# Control.net
KiCad netlist of a schematic drawn in EasyEDA Pro
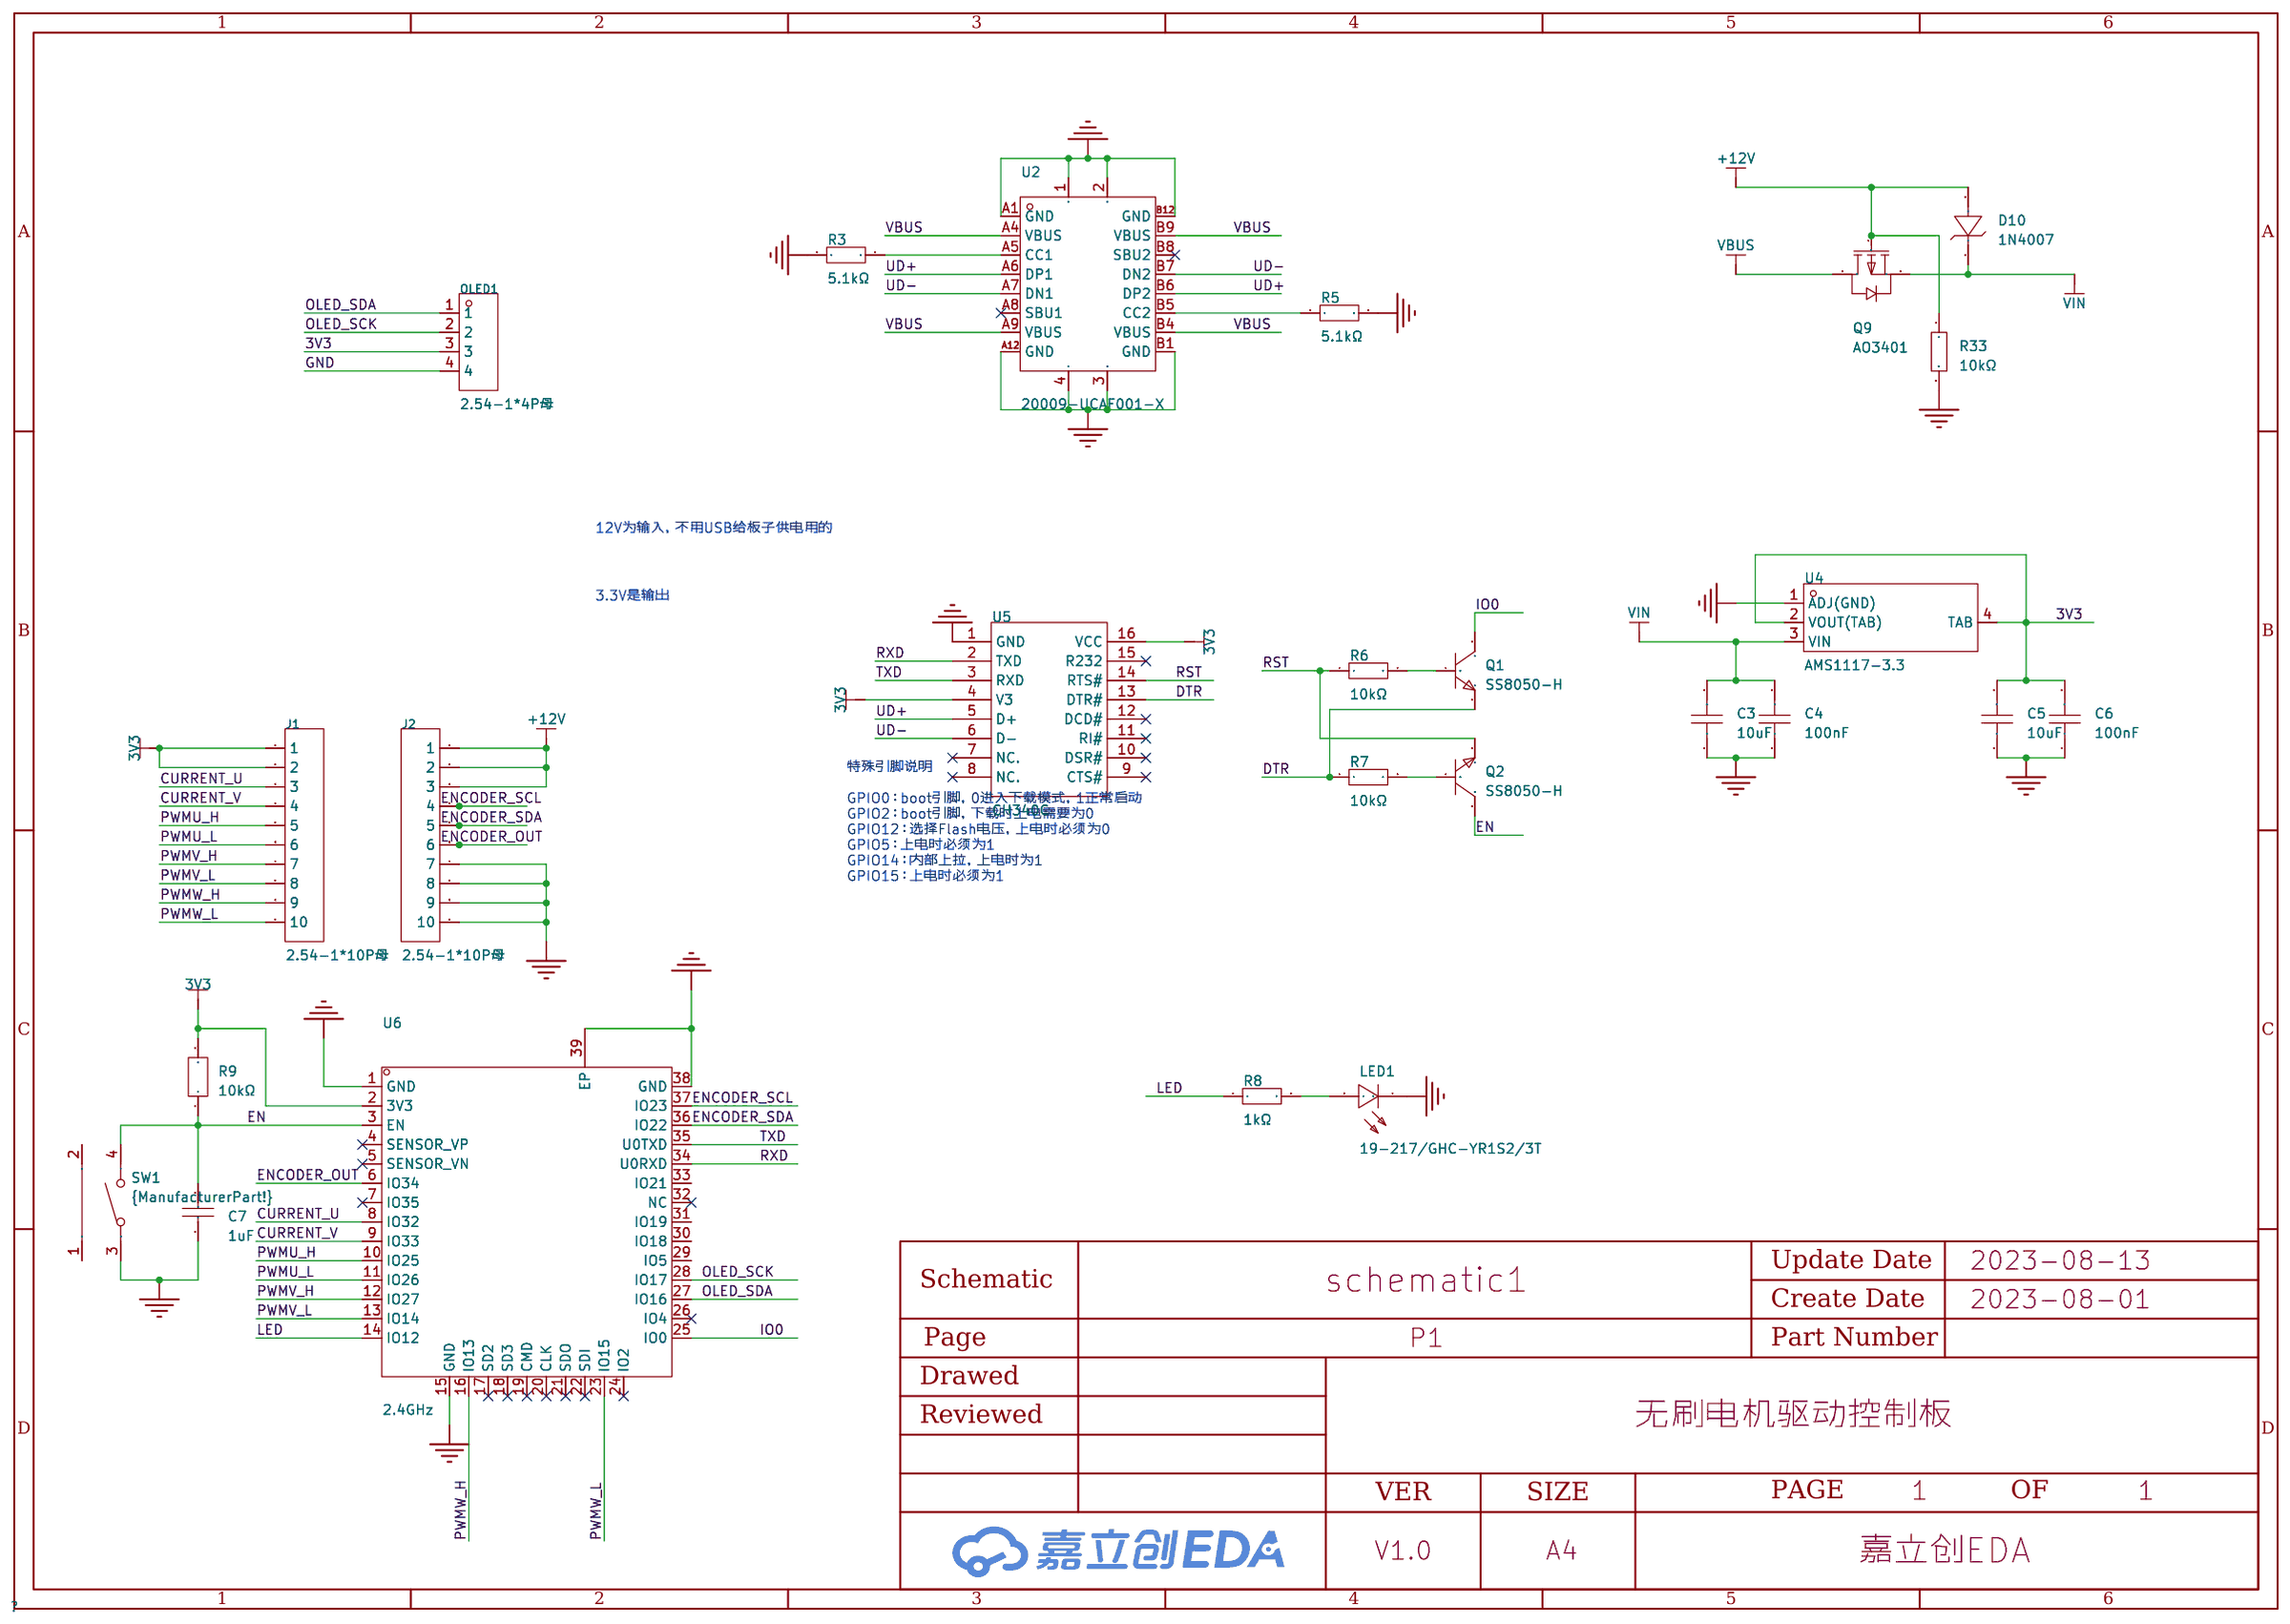
[diagram p0: schematic sheet]

(export (version "E")
  (design (tool "Eeschema 10.0.6"))
  (components
    (comp (ref "C3")
      (value "10uF")
      (footprint "easyedapro:C0603")
      (description "容值:10uF;精度:±20%;额定电压:25V;材质(温度系数):X5R;")
      (fields
        (field (name "Manufacturer Part") "CL10A106MA8NRNC")
        (field (name "Manufacturer") "SAMSUNG(三星)")
      )
      (libsource (lib "easyedapro") (part "CL10A106MA8NRNC"))
    )
    (comp (ref "C4")
      (value "100nF")
      (footprint "easyedapro:C0603")
      (description "容值:100nF;精度:±10%;额定电压:50V;材质(温度系数):X7R;")
      (fields
        (field (name "Manufacturer Part") "CC0603KRX7R9BB104")
        (field (name "Manufacturer") "YAGEO(国巨)")
      )
      (libsource (lib "easyedapro") (part "CC0603KRX7R9BB104"))
    )
    (comp (ref "C5")
      (value "10uF")
      (footprint "easyedapro:C0603")
      (description "容值:10uF;精度:±20%;额定电压:25V;材质(温度系数):X5R;")
      (fields
        (field (name "Manufacturer Part") "CL10A106MA8NRNC")
        (field (name "Manufacturer") "SAMSUNG(三星)")
      )
      (libsource (lib "easyedapro") (part "CL10A106MA8NRNC"))
    )
    (comp (ref "C6")
      (value "100nF")
      (footprint "easyedapro:C0603")
      (description "容值:100nF;精度:±10%;额定电压:50V;材质(温度系数):X7R;")
      (fields
        (field (name "Manufacturer Part") "CC0603KRX7R9BB104")
        (field (name "Manufacturer") "YAGEO(国巨)")
      )
      (libsource (lib "easyedapro") (part "CC0603KRX7R9BB104"))
    )
    (comp (ref "C7")
      (value "1uF")
      (footprint "easyedapro:C0603")
      (description "容值:1uF;精度:±10%;额定电压:50V;材质(温度系数):X5R;")
      (fields
        (field (name "Manufacturer Part") "CL10A105KB8NNNC")
        (field (name "Manufacturer") "SAMSUNG(三星)")
      )
      (libsource (lib "easyedapro") (part "CL10A105KB8NNNC"))
    )
    (comp (ref "D10")
      (value "1N4007")
      (footprint "easyedapro:SOD-123FL_L2.7-W1.8-LS3.8-RD")
      (description "二极管配置:独立式;直流反向耐压(Vr):1kV;平均整流电流(Io):1A;正向压降(Vf):1.1V@1A;反向电流(Ir):10uA@1kV;")
      (fields (field (name "Manufacturer") "TWGMC(台湾迪嘉)"))
      (libsource (lib "easyedapro") (part "1N4007_C727082"))
    )
    (comp (ref "J1")
      (value "2.54-1*10P母")
      (footprint "easyedapro:HDR-TH_10P-P2.54-V-F")
      (description "排数:单排;总孔位数:10;间距:2.54mm;插孔结构:1x10P;行距:-;安装类型:直插;塑高:-;触头材质:-;触头镀层:-;")
      (fields (field (name "Manufacturer") "BOOMELE(博穆精密)"))
      (libsource (lib "easyedapro") (part "Header-Female-2.54_1x10"))
    )
    (comp (ref "J2")
      (value "2.54-1*10P母")
      (footprint "easyedapro:HDR-TH_10P-P2.54-V-F")
      (description "排数:单排;总孔位数:10;间距:2.54mm;插孔结构:1x10P;行距:-;安装类型:直插;塑高:-;触头材质:-;触头镀层:-;")
      (fields (field (name "Manufacturer") "BOOMELE(博穆精密)"))
      (libsource (lib "easyedapro") (part "Header-Female-2.54_1x10"))
    )
    (comp (ref "LED1")
      (value "19-217/GHC-YR1S2/3T")
      (footprint "easyedapro:LED0603-RD")
      (description "发光颜色:翠绿;二极管配置:-;主波长:520nm~535nm;色温:-;功率:110mW;安装方式:-;")
      (fields (field (name "Manufacturer") "EVERLIGHT(亿光)"))
      (libsource (lib "easyedapro") (part "19-217/GHC-YR1S2/3T"))
    )
    (comp (ref "OLED1")
      (value "2.54-1*4P母")
      (footprint "easyedapro:HDR-TH_4P-P2.54-V-F")
      (fields (field (name "Manufacturer") "BOOMELE(博穆精密)"))
      (libsource (lib "easyedapro") (part "2.54-1*4P母"))
    )
    (comp (ref "Q1")
      (value "SS8050-H")
      (footprint "easyedapro:SOT-23-3_L2.9-W1.3-P1.90-LS2.4-BR")
      (description "晶体管类型:NPN;集射极击穿电压(Vceo):25V;集电极电流(Ic):1.5A;功率(Pd):300mW;直流电流增益(hFE@Ic,Vce):200@100mA,1V;")
      (fields (field (name "Manufacturer") "YANGJIE(扬杰)"))
      (libsource (lib "easyedapro") (part "SS8050-H"))
    )
    (comp (ref "Q2")
      (value "SS8050-H")
      (footprint "easyedapro:SOT-23-3_L2.9-W1.3-P1.90-LS2.4-BR")
      (description "晶体管类型:NPN;集射极击穿电压(Vceo):25V;集电极电流(Ic):1.5A;功率(Pd):300mW;直流电流增益(hFE@Ic,Vce):200@100mA,1V;")
      (fields (field (name "Manufacturer") "YANGJIE(扬杰)"))
      (libsource (lib "easyedapro") (part "SS8050-H"))
    )
    (comp (ref "Q9")
      (value "AO3401")
      (footprint "easyedapro:SOT-23-3_L2.9-W1.4-P1.90-LS2.6-BR")
      (description "类型:P沟道;漏源电压(Vdss):30V;连续漏极电流(Id):4.2A;功率(Pd):350mW;导通电阻(RDS(on)@Vgs,Id):65mΩ@10V,4.2A;")
      (fields (field (name "Manufacturer") "TWGMC(台湾迪嘉)"))
      (libsource (lib "easyedapro") (part "AO3401_C727156"))
    )
    (comp (ref "R3")
      (value "5.1kΩ")
      (footprint "easyedapro:R0603")
      (description "电阻类型:厚膜电阻;阻值:5.1kΩ;精度:±1%;功率:100mW;")
      (fields
        (field (name "Manufacturer Part") "0603WAF5101T5E")
        (field (name "Manufacturer") "UNI-ROYAL(厚声)")
      )
      (libsource (lib "easyedapro") (part "0603WAF5101T5E"))
    )
    (comp (ref "R5")
      (value "5.1kΩ")
      (footprint "easyedapro:R0603")
      (description "电阻类型:厚膜电阻;阻值:5.1kΩ;精度:±1%;功率:100mW;")
      (fields
        (field (name "Manufacturer Part") "0603WAF5101T5E")
        (field (name "Manufacturer") "UNI-ROYAL(厚声)")
      )
      (libsource (lib "easyedapro") (part "0603WAF5101T5E"))
    )
    (comp (ref "R6")
      (value "10kΩ")
      (footprint "easyedapro:R0603")
      (description "电阻类型:厚膜电阻;阻值:10kΩ;精度:±1%;功率:100mW;")
      (fields (field (name "Manufacturer Part") "ERJ3EKF1002V") (field (name "Manufacturer") "PANASONIC(松下)"))
      (libsource (lib "easyedapro") (part "ERJ-3EKF1002V"))
    )
    (comp (ref "R7")
      (value "10kΩ")
      (footprint "easyedapro:R0603")
      (description "电阻类型:厚膜电阻;阻值:10kΩ;精度:±1%;功率:100mW;")
      (fields (field (name "Manufacturer Part") "ERJ3EKF1002V") (field (name "Manufacturer") "PANASONIC(松下)"))
      (libsource (lib "easyedapro") (part "ERJ-3EKF1002V"))
    )
    (comp (ref "R8")
      (value "1kΩ")
      (footprint "easyedapro:R0603")
      (description "电阻类型:厚膜电阻;阻值:1kΩ;精度:±1%;功率:100mW;")
      (fields
        (field (name "Manufacturer Part") "0603WAF1001T5E")
        (field (name "Manufacturer") "UNI-ROYAL(厚声)")
      )
      (libsource (lib "easyedapro") (part "0603WAF1001T5E"))
    )
    (comp (ref "R9")
      (value "10kΩ")
      (footprint "easyedapro:R0603")
      (description "阻值:10kΩ;精度:±1%;功率:-;")
      (fields (field (name "Manufacturer Part") "SG73P1JTTD1002F") (field (name "Manufacturer") "KOA"))
      (libsource (lib "easyedapro") (part "SG73P1JTTD1002F"))
    )
    (comp (ref "R33")
      (value "10kΩ")
      (footprint "easyedapro:R0603")
      (description "电阻类型:厚膜电阻;阻值:10kΩ;精度:±1%;功率:100mW;")
      (fields
        (field (name "Manufacturer Part") "0603WAF1002T5E")
        (field (name "Manufacturer") "UNI-ROYAL(厚声)")
      )
      (libsource (lib "easyedapro") (part "0603WAF1002T5E"))
    )
    (comp (ref "SW1")
      (value "{ManufacturerPart!}")
      (footprint "easyedapro:SW-SMD_TS24CA")
      (description "触点电流:50mA;额定电压(DC):12V;电路结构:单刀单掷;安装方式:卧贴;带灯:-;机械寿命:-;")
      (fields (field (name "Manufacturer Part") "TS24CA") (field (name "Manufacturer") "SHOUHAN(首韩)"))
      (libsource (lib "easyedapro") (part "TS24CA"))
    )
    (comp (ref "U2")
      (value "20009-UCAF001-X")
      (footprint "easyedapro:TYPE-C-SMD_20009-UCAF001-X")
      (fields (field (name "Manufacturer") "MINTRON(明硕)"))
      (libsource (lib "easyedapro") (part "20009-UCAF001-X"))
    )
    (comp (ref "U4")
      (value "AMS1117-3.3")
      (footprint "easyedapro:SOT-223-4_L6.5-W3.5-P2.30-LS7.0-BR")
      (description "输出类型:固定;输出极性:正;最大输入电压:18V;输出电压:3.3V;输出电流:1A;电源纹波抑制比(PSRR):60dB@(120Hz);")
      (fields (field (name "Manufacturer") "UMW(广东友台半导体)"))
      (libsource (lib "easyedapro") (part "AMS1117-3.3_C347222"))
    )
    (comp (ref "U5")
      (value "CH340C")
      (footprint "easyedapro:SOP-16_L10.0-W3.9-P1.27-LS6.0-BL")
      (description "应用功能:Transceiver;接口协议:USB 2.0;数据速率:2Mbps;供电电压:3.3V；5V;")
      (fields (field (name "Manufacturer") "WCH(南京沁恒)"))
      (libsource (lib "easyedapro") (part "CH340C"))
    )
    (comp (ref "U6")
      (value "2.4GHz")
      (footprint "easyedapro:WIRELM-SMD_ESP32-S")
      (description "频率:2.4GHz;发射功率:17dBm;核心处理器:LX6;天线形式:板载 PCB 天线/外接 IPEX;接收灵敏度:-90dBm;")
      (fields (field (name "Manufacturer Part") "ESP32-S") (field (name "Manufacturer") "Ai-Thinker(安信可)"))
      (libsource (lib "easyedapro") (part "ESP32-S"))
    )
  )
  (nets
    (net (code "1") (name "+12V") (class "Default")
      (node (ref "D10") (pin "2") (pinfunction "A_2") (pintype "input"))
      (node (ref "J2") (pin "1") (pinfunction "1_1") (pintype "input"))
      (node (ref "J2") (pin "2") (pinfunction "2_2") (pintype "input"))
      (node (ref "J2") (pin "3") (pinfunction "3_3") (pintype "input"))
      (node (ref "Q9") (pin "1") (pinfunction "G_1") (pintype "input"))
      (node (ref "R33") (pin "1") (pinfunction "1_1") (pintype "input"))
    )
    (net (code "2") (name "/CURRENT_U") (class "Default")
      (node (ref "J1") (pin "3") (pinfunction "3_3") (pintype "input"))
      (node (ref "U6") (pin "8") (pinfunction "IO32_8") (pintype "input"))
    )
    (net (code "3") (name "/CURRENT_V") (class "Default")
      (node (ref "J1") (pin "4") (pinfunction "4_4") (pintype "input"))
      (node (ref "U6") (pin "9") (pinfunction "IO33_9") (pintype "input"))
    )
    (net (code "4") (name "/DTR") (class "Default")
      (node (ref "Q1") (pin "2") (pinfunction "E_2") (pintype "input"))
      (node (ref "R7") (pin "1") (pinfunction "1_1") (pintype "input"))
      (node (ref "U5") (pin "13") (pinfunction "DTR#_13") (pintype "input"))
    )
    (net (code "5") (name "/EN") (class "Default")
      (node (ref "C7") (pin "2") (pinfunction "2_2") (pintype "input"))
      (node (ref "Q2") (pin "3") (pinfunction "C_3") (pintype "input"))
      (node (ref "R9") (pin "1") (pinfunction "1_1") (pintype "input"))
      (node (ref "SW1") (pin "4") (pinfunction "4_4") (pintype "input"))
      (node (ref "U6") (pin "3") (pinfunction "EN_3") (pintype "input"))
    )
    (net (code "6") (name "/ENCODER_OUT") (class "Default")
      (node (ref "J2") (pin "6") (pinfunction "6_6") (pintype "input"))
      (node (ref "U6") (pin "6") (pinfunction "IO34_6") (pintype "input"))
    )
    (net (code "7") (name "/ENCODER_SCL") (class "Default")
      (node (ref "J2") (pin "4") (pinfunction "4_4") (pintype "input"))
      (node (ref "U6") (pin "37") (pinfunction "IO23_37") (pintype "input"))
    )
    (net (code "8") (name "/ENCODER_SDA") (class "Default")
      (node (ref "J2") (pin "5") (pinfunction "5_5") (pintype "input"))
      (node (ref "U6") (pin "36") (pinfunction "IO22_36") (pintype "input"))
    )
    (net (code "9") (name "/IO0") (class "Default")
      (node (ref "Q1") (pin "3") (pinfunction "C_3") (pintype "input"))
      (node (ref "U6") (pin "25") (pinfunction "IO0_25") (pintype "input"))
    )
    (net (code "10") (name "/LED") (class "Default")
      (node (ref "R8") (pin "1") (pinfunction "1_1") (pintype "input"))
      (node (ref "U6") (pin "14") (pinfunction "IO12_14") (pintype "input"))
    )
    (net (code "11") (name "/OLED_SCK") (class "Default")
      (node (ref "OLED1") (pin "2") (pinfunction "2_2") (pintype "input"))
      (node (ref "U6") (pin "28") (pinfunction "IO17_28") (pintype "input"))
    )
    (net (code "12") (name "/OLED_SDA") (class "Default")
      (node (ref "OLED1") (pin "1") (pinfunction "1_1") (pintype "input"))
      (node (ref "U6") (pin "27") (pinfunction "IO16_27") (pintype "input"))
    )
    (net (code "13") (name "/PWMU_H") (class "Default")
      (node (ref "J1") (pin "5") (pinfunction "5_5") (pintype "input"))
      (node (ref "U6") (pin "10") (pinfunction "IO25_10") (pintype "input"))
    )
    (net (code "14") (name "/PWMU_L") (class "Default")
      (node (ref "J1") (pin "6") (pinfunction "6_6") (pintype "input"))
      (node (ref "U6") (pin "11") (pinfunction "IO26_11") (pintype "input"))
    )
    (net (code "15") (name "/PWMV_H") (class "Default")
      (node (ref "J1") (pin "7") (pinfunction "7_7") (pintype "input"))
      (node (ref "U6") (pin "12") (pinfunction "IO27_12") (pintype "input"))
    )
    (net (code "16") (name "/PWMV_L") (class "Default")
      (node (ref "J1") (pin "8") (pinfunction "8_8") (pintype "input"))
      (node (ref "U6") (pin "13") (pinfunction "IO14_13") (pintype "input"))
    )
    (net (code "17") (name "/PWMW_H") (class "Default")
      (node (ref "J1") (pin "9") (pinfunction "9_9") (pintype "input"))
      (node (ref "U6") (pin "16") (pinfunction "IO13_16") (pintype "input"))
    )
    (net (code "18") (name "/PWMW_L") (class "Default")
      (node (ref "J1") (pin "10") (pinfunction "10_10") (pintype "input"))
      (node (ref "U6") (pin "23") (pinfunction "IO15_23") (pintype "input"))
    )
    (net (code "19") (name "/RST") (class "Default")
      (node (ref "Q2") (pin "2") (pinfunction "E_2") (pintype "input"))
      (node (ref "R6") (pin "1") (pinfunction "1_1") (pintype "input"))
      (node (ref "U5") (pin "14") (pinfunction "RTS#_14") (pintype "input"))
    )
    (net (code "20") (name "/RXD") (class "Default")
      (node (ref "U5") (pin "2") (pinfunction "TXD_2") (pintype "input"))
      (node (ref "U6") (pin "34") (pinfunction "U0RXD_34") (pintype "input"))
    )
    (net (code "21") (name "/TXD") (class "Default")
      (node (ref "U5") (pin "3") (pinfunction "RXD_3") (pintype "input"))
      (node (ref "U6") (pin "35") (pinfunction "U0TXD_35") (pintype "input"))
    )
    (net (code "22") (name "/UD+") (class "Default")
      (node (ref "U2") (pin "A6") (pinfunction "DP1_A6") (pintype "input"))
      (node (ref "U2") (pin "B6") (pinfunction "DP2_B6") (pintype "input"))
      (node (ref "U5") (pin "5") (pinfunction "D+_5") (pintype "input"))
    )
    (net (code "23") (name "/UD-") (class "Default")
      (node (ref "U2") (pin "A7") (pinfunction "DN1_A7") (pintype "input"))
      (node (ref "U2") (pin "B7") (pinfunction "DN2_B7") (pintype "input"))
      (node (ref "U5") (pin "6") (pinfunction "D-_6") (pintype "input"))
    )
    (net (code "24") (name "3V3") (class "Default")
      (node (ref "C5") (pin "2") (pinfunction "2_2") (pintype "input"))
      (node (ref "C6") (pin "2") (pinfunction "2_2") (pintype "input"))
      (node (ref "J1") (pin "1") (pinfunction "1_1") (pintype "input"))
      (node (ref "J1") (pin "2") (pinfunction "2_2") (pintype "input"))
      (node (ref "OLED1") (pin "3") (pinfunction "3_3") (pintype "input"))
      (node (ref "R9") (pin "2") (pinfunction "2_2") (pintype "input"))
      (node (ref "U4") (pin "2") (pinfunction "VOUT(TAB)_2") (pintype "input"))
      (node (ref "U4") (pin "4") (pinfunction "TAB_4") (pintype "input"))
      (node (ref "U5") (pin "16") (pinfunction "VCC_16") (pintype "input"))
      (node (ref "U5") (pin "4") (pinfunction "V3_4") (pintype "input"))
      (node (ref "U6") (pin "2") (pinfunction "3V3_2") (pintype "input"))
    )
    (net (code "25") (name "GND") (class "Default")
      (node (ref "C3") (pin "1") (pinfunction "1_1") (pintype "input"))
      (node (ref "C4") (pin "1") (pinfunction "1_1") (pintype "input"))
      (node (ref "C5") (pin "1") (pinfunction "1_1") (pintype "input"))
      (node (ref "C6") (pin "1") (pinfunction "1_1") (pintype "input"))
      (node (ref "C7") (pin "1") (pinfunction "1_1") (pintype "input"))
      (node (ref "J2") (pin "10") (pinfunction "10_10") (pintype "input"))
      (node (ref "J2") (pin "7") (pinfunction "7_7") (pintype "input"))
      (node (ref "J2") (pin "8") (pinfunction "8_8") (pintype "input"))
      (node (ref "J2") (pin "9") (pinfunction "9_9") (pintype "input"))
      (node (ref "LED1") (pin "1") (pinfunction "C_1") (pintype "input"))
      (node (ref "OLED1") (pin "4") (pinfunction "4_4") (pintype "input"))
      (node (ref "R3") (pin "1") (pinfunction "1_1") (pintype "input"))
      (node (ref "R33") (pin "2") (pinfunction "2_2") (pintype "input"))
      (node (ref "R5") (pin "2") (pinfunction "2_2") (pintype "input"))
      (node (ref "SW1") (pin "3") (pinfunction "3_3") (pintype "input"))
      (node (ref "U2") (pin "1") (pinfunction "1_1") (pintype "input"))
      (node (ref "U2") (pin "2") (pinfunction "2_2") (pintype "input"))
      (node (ref "U2") (pin "3") (pinfunction "3_3") (pintype "input"))
      (node (ref "U2") (pin "4") (pinfunction "4_4") (pintype "input"))
      (node (ref "U2") (pin "A1") (pinfunction "GND_A1") (pintype "input"))
      (node (ref "U2") (pin "A12") (pinfunction "GND_A12") (pintype "input"))
      (node (ref "U2") (pin "B1") (pinfunction "GND_B1") (pintype "input"))
      (node (ref "U2") (pin "B12") (pinfunction "GND_B12") (pintype "input"))
      (node (ref "U4") (pin "1") (pinfunction "ADJ(GND)_1") (pintype "input"))
      (node (ref "U5") (pin "1") (pinfunction "GND_1") (pintype "input"))
      (node (ref "U6") (pin "1") (pinfunction "GND_1") (pintype "input"))
      (node (ref "U6") (pin "15") (pinfunction "GND_15") (pintype "input"))
      (node (ref "U6") (pin "38") (pinfunction "GND_38") (pintype "input"))
      (node (ref "U6") (pin "39") (pinfunction "EP_39") (pintype "input"))
    )
    (net (code "26") (name "Net-(LED1-A)") (class "Default")
      (node (ref "LED1") (pin "2") (pinfunction "A_2") (pintype "input"))
      (node (ref "R8") (pin "2") (pinfunction "2_2") (pintype "input"))
    )
    (net (code "27") (name "Net-(Q1-B)") (class "Default")
      (node (ref "Q1") (pin "1") (pinfunction "B_1") (pintype "input"))
      (node (ref "R6") (pin "2") (pinfunction "2_2") (pintype "input"))
    )
    (net (code "28") (name "Net-(Q2-B)") (class "Default")
      (node (ref "Q2") (pin "1") (pinfunction "B_1") (pintype "input"))
      (node (ref "R7") (pin "2") (pinfunction "2_2") (pintype "input"))
    )
    (net (code "29") (name "Net-(U2-CC1)") (class "Default")
      (node (ref "R3") (pin "2") (pinfunction "2_2") (pintype "input"))
      (node (ref "U2") (pin "A5") (pinfunction "CC1_A5") (pintype "input"))
    )
    (net (code "30") (name "Net-(U2-CC2)") (class "Default")
      (node (ref "R5") (pin "1") (pinfunction "1_1") (pintype "input"))
      (node (ref "U2") (pin "B5") (pinfunction "CC2_B5") (pintype "input"))
    )
    (net (code "31") (name "VBUS") (class "Default")
      (node (ref "Q9") (pin "3") (pinfunction "D_3") (pintype "input"))
      (node (ref "U2") (pin "A4") (pinfunction "VBUS_A4") (pintype "input"))
      (node (ref "U2") (pin "A9") (pinfunction "VBUS_A9") (pintype "input"))
      (node (ref "U2") (pin "B4") (pinfunction "VBUS_B4") (pintype "input"))
      (node (ref "U2") (pin "B9") (pinfunction "VBUS_B9") (pintype "input"))
    )
    (net (code "32") (name "VIN") (class "Default")
      (node (ref "C3") (pin "2") (pinfunction "2_2") (pintype "input"))
      (node (ref "C4") (pin "2") (pinfunction "2_2") (pintype "input"))
      (node (ref "D10") (pin "1") (pinfunction "K_1") (pintype "input"))
      (node (ref "Q9") (pin "2") (pinfunction "S_2") (pintype "input"))
      (node (ref "U4") (pin "3") (pinfunction "VIN_3") (pintype "input"))
    )
    (net (code "33") (name "unconnected-(SW1-Pad1)") (class "Default")
      (node (ref "SW1") (pin "1") (pinfunction "1_1") (pintype "input"))
    )
    (net (code "34") (name "unconnected-(SW1-Pad2)") (class "Default")
      (node (ref "SW1") (pin "2") (pinfunction "2_2") (pintype "input"))
    )
    (net (code "35") (name "unconnected-(U2-SBU1-PadA8)") (class "Default")
      (node (ref "U2") (pin "A8") (pinfunction "SBU1_A8") (pintype "input+no_connect"))
    )
    (net (code "36") (name "unconnected-(U2-SBU2-PadB8)") (class "Default")
      (node (ref "U2") (pin "B8") (pinfunction "SBU2_B8") (pintype "input+no_connect"))
    )
    (net (code "37") (name "unconnected-(U5-CTS#-Pad9)") (class "Default")
      (node (ref "U5") (pin "9") (pinfunction "CTS#_9") (pintype "input+no_connect"))
    )
    (net (code "38") (name "unconnected-(U5-DCD#-Pad12)") (class "Default")
      (node (ref "U5") (pin "12") (pinfunction "DCD#_12") (pintype "input+no_connect"))
    )
    (net (code "39") (name "unconnected-(U5-DSR#-Pad10)") (class "Default")
      (node (ref "U5") (pin "10") (pinfunction "DSR#_10") (pintype "input+no_connect"))
    )
    (net (code "40") (name "unconnected-(U5-NC.-Pad7)") (class "Default")
      (node (ref "U5") (pin "7") (pinfunction "NC._7") (pintype "input+no_connect"))
    )
    (net (code "41") (name "unconnected-(U5-NC.-Pad8)") (class "Default")
      (node (ref "U5") (pin "8") (pinfunction "NC._8") (pintype "input+no_connect"))
    )
    (net (code "42") (name "unconnected-(U5-R232-Pad15)") (class "Default")
      (node (ref "U5") (pin "15") (pinfunction "R232_15") (pintype "input+no_connect"))
    )
    (net (code "43") (name "unconnected-(U5-RI#-Pad11)") (class "Default")
      (node (ref "U5") (pin "11") (pinfunction "RI#_11") (pintype "input+no_connect"))
    )
    (net (code "44") (name "unconnected-(U6-CLK-Pad20)") (class "Default")
      (node (ref "U6") (pin "20") (pinfunction "CLK_20") (pintype "input+no_connect"))
    )
    (net (code "45") (name "unconnected-(U6-CMD-Pad19)") (class "Default")
      (node (ref "U6") (pin "19") (pinfunction "CMD_19") (pintype "input+no_connect"))
    )
    (net (code "46") (name "unconnected-(U6-IO2-Pad24)") (class "Default")
      (node (ref "U6") (pin "24") (pinfunction "IO2_24") (pintype "input+no_connect"))
    )
    (net (code "47") (name "unconnected-(U6-IO4-Pad26)") (class "Default")
      (node (ref "U6") (pin "26") (pinfunction "IO4_26") (pintype "input+no_connect"))
    )
    (net (code "48") (name "unconnected-(U6-IO5-Pad29)") (class "Default")
      (node (ref "U6") (pin "29") (pinfunction "IO5_29") (pintype "input"))
    )
    (net (code "49") (name "unconnected-(U6-IO18-Pad30)") (class "Default")
      (node (ref "U6") (pin "30") (pinfunction "IO18_30") (pintype "input"))
    )
    (net (code "50") (name "unconnected-(U6-IO19-Pad31)") (class "Default")
      (node (ref "U6") (pin "31") (pinfunction "IO19_31") (pintype "input"))
    )
    (net (code "51") (name "unconnected-(U6-IO21-Pad33)") (class "Default")
      (node (ref "U6") (pin "33") (pinfunction "IO21_33") (pintype "input"))
    )
    (net (code "52") (name "unconnected-(U6-IO35-Pad7)") (class "Default")
      (node (ref "U6") (pin "7") (pinfunction "IO35_7") (pintype "input+no_connect"))
    )
    (net (code "53") (name "unconnected-(U6-NC-Pad32)") (class "Default")
      (node (ref "U6") (pin "32") (pinfunction "NC_32") (pintype "input+no_connect"))
    )
    (net (code "54") (name "unconnected-(U6-SD2-Pad17)") (class "Default")
      (node (ref "U6") (pin "17") (pinfunction "SD2_17") (pintype "input+no_connect"))
    )
    (net (code "55") (name "unconnected-(U6-SD3-Pad18)") (class "Default")
      (node (ref "U6") (pin "18") (pinfunction "SD3_18") (pintype "input+no_connect"))
    )
    (net (code "56") (name "unconnected-(U6-SDI-Pad22)") (class "Default")
      (node (ref "U6") (pin "22") (pinfunction "SDI_22") (pintype "input+no_connect"))
    )
    (net (code "57") (name "unconnected-(U6-SDO-Pad21)") (class "Default")
      (node (ref "U6") (pin "21") (pinfunction "SDO_21") (pintype "input+no_connect"))
    )
    (net (code "58") (name "unconnected-(U6-SENSOR_VN-Pad5)") (class "Default")
      (node (ref "U6") (pin "5") (pinfunction "SENSOR_VN_5") (pintype "input+no_connect"))
    )
    (net (code "59") (name "unconnected-(U6-SENSOR_VP-Pad4)") (class "Default")
      (node (ref "U6") (pin "4") (pinfunction "SENSOR_VP_4") (pintype "input+no_connect"))
    )
  )
)
